# Cobro_Torniquete.net
KiCad netlist of a schematic drawn in EAGLE
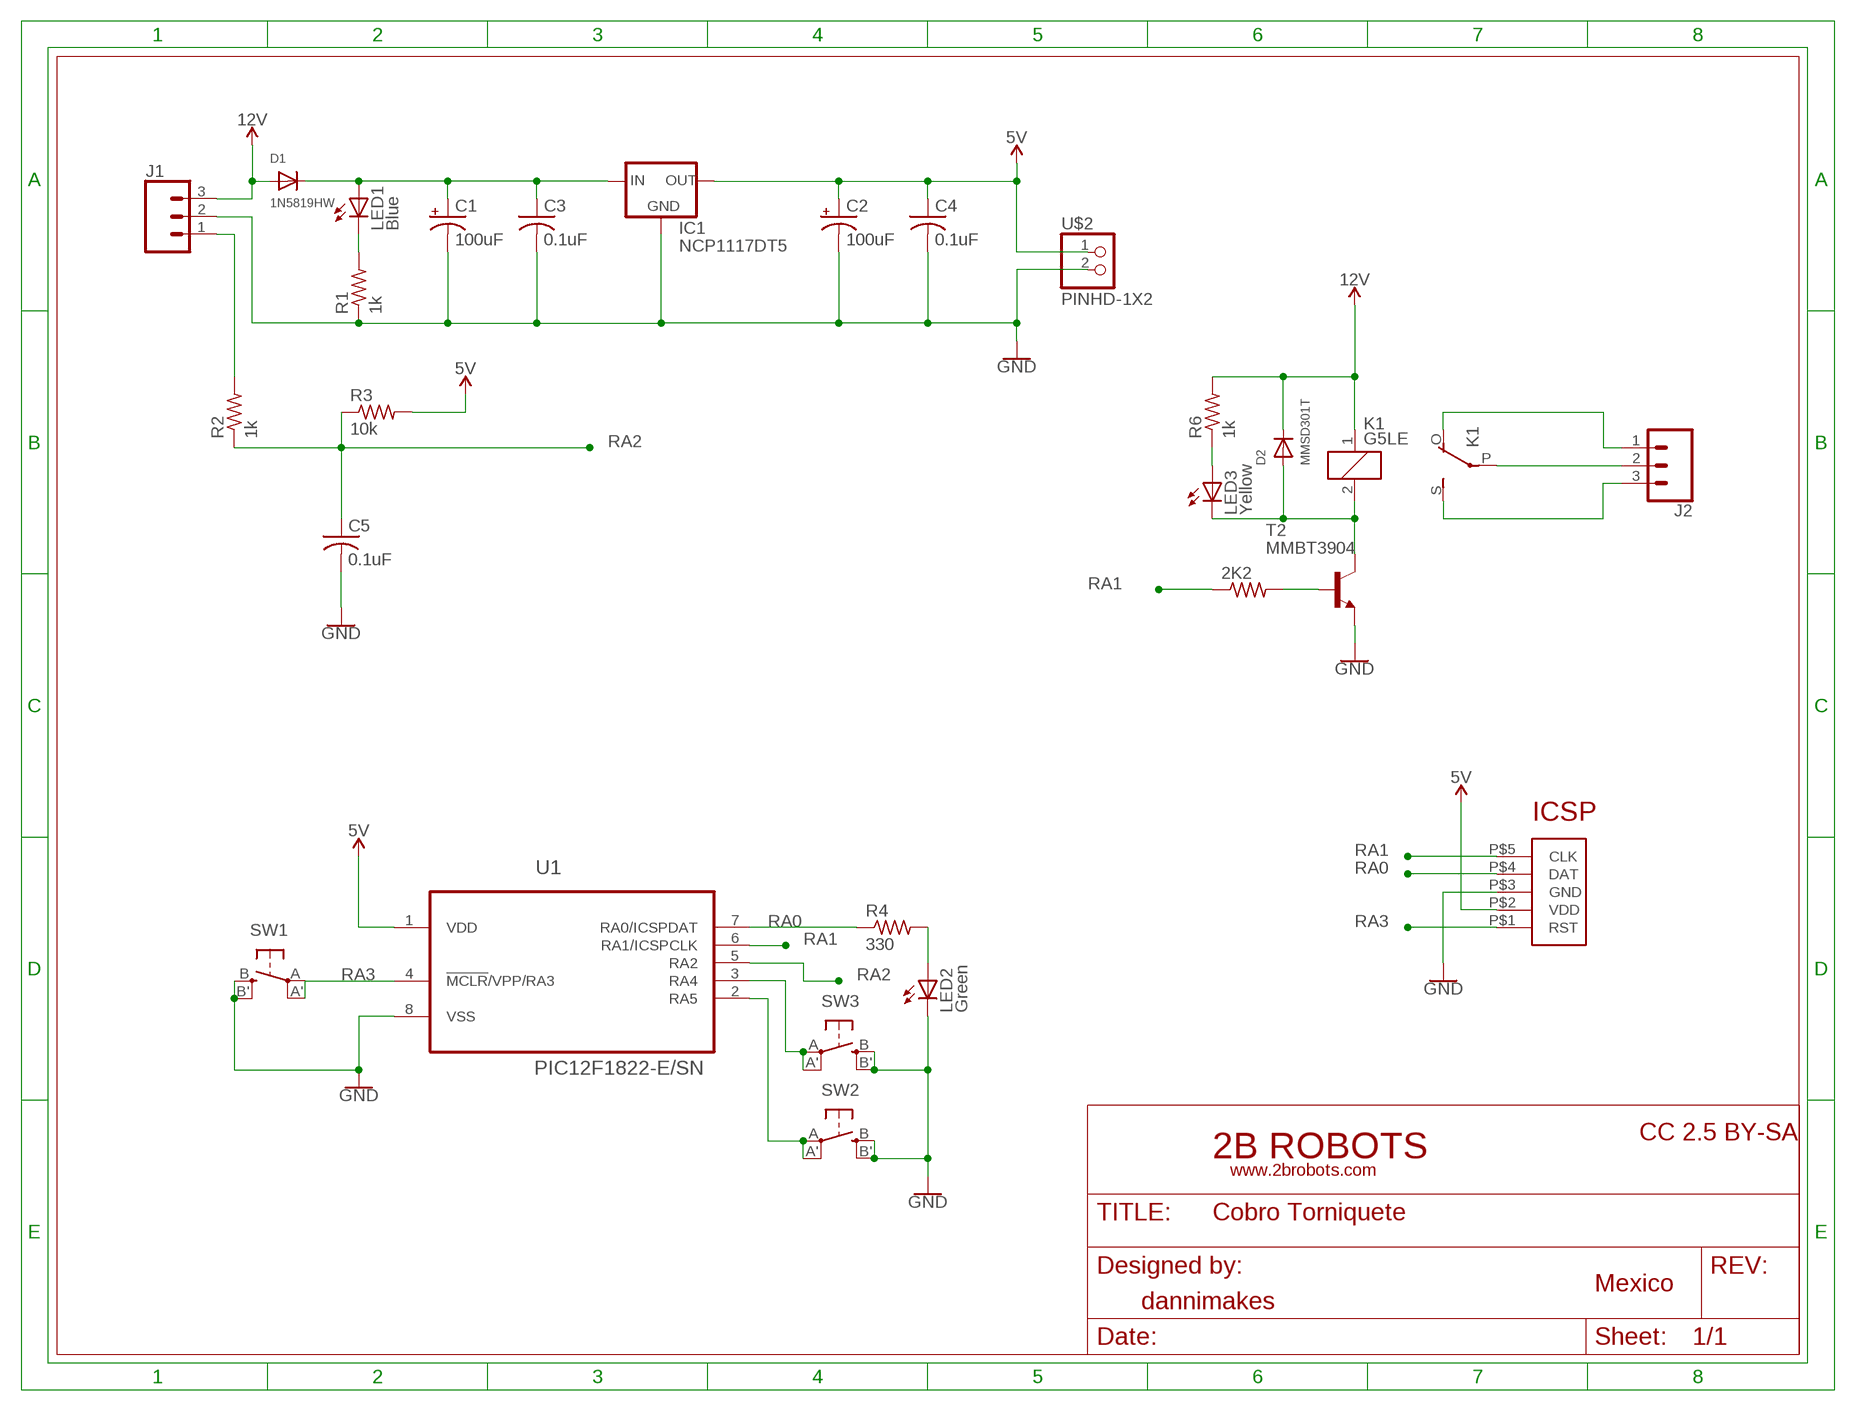
[diagram p0: schematic, sheet 1]

(export (version "E")
  (design (tool "Eeschema 10.0.6"))
  (components
    (comp (ref "2K2")
      (value "R-US_R0805")
      (footprint "eagle-import:R0805")
      (libsource (lib "eagle-import") (part "R-US_R0805"))
    )
    (comp (ref "C1")
      (value "100uF")
      (footprint "eagle-import:140CLH-0810")
      (libsource (lib "eagle-import") (part "CPOL-US140CLH-0810"))
    )
    (comp (ref "C2")
      (value "100uF")
      (footprint "eagle-import:140CLH-0810")
      (libsource (lib "eagle-import") (part "CPOL-US140CLH-0810"))
    )
    (comp (ref "C3")
      (value "0.1uF")
      (footprint "eagle-import:C0603K")
      (libsource (lib "eagle-import") (part "C-USC0603K"))
    )
    (comp (ref "C4")
      (value "0.1uF")
      (footprint "eagle-import:C0603K")
      (libsource (lib "eagle-import") (part "C-USC0603K"))
    )
    (comp (ref "C5")
      (value "0.1uF")
      (footprint "eagle-import:C0603K")
      (libsource (lib "eagle-import") (part "C-USC0603K"))
    )
    (comp (ref "D1")
      (value "1N5819HW")
      (footprint "eagle-import:SOD-123")
      (libsource (lib "eagle-import") (part "DIODESOD-123"))
    )
    (comp (ref "D2")
      (value "MMSD301T")
      (footprint "eagle-import:SOD-123")
      (libsource (lib "eagle-import") (part "DIODESOD-123"))
    )
    (comp (ref "IC1")
      (value "NCP1117DT5")
      (footprint "eagle-import:TO252")
      (libsource (lib "eagle-import") (part "LM1117TO252"))
    )
    (comp (ref "J1")
      (value "CONN_03-SCREW-5MM")
      (footprint "eagle-import:SCREWTERMINAL-5MM-3")
      (libsource (lib "eagle-import") (part "CONN_03-SCREW-5MM"))
    )
    (comp (ref "J2")
      (value "CONN_03-SCREW-5MM")
      (footprint "eagle-import:SCREWTERMINAL-5MM-3")
      (libsource (lib "eagle-import") (part "CONN_03-SCREW-5MM"))
    )
    (comp (ref "K1")
      (value "G5LE")
      (footprint "eagle-import:G5LE")
      (libsource (lib "eagle-import") (part "G5LE"))
    )
    (comp (ref "LED1")
      (value "Blue")
      (footprint "eagle-import:CHIPLED_1206")
      (libsource (lib "eagle-import") (part "LEDCHIPLED_1206"))
    )
    (comp (ref "LED2")
      (value "Green")
      (footprint "eagle-import:CHIPLED_1206")
      (libsource (lib "eagle-import") (part "LEDCHIPLED_1206"))
    )
    (comp (ref "LED3")
      (value "Yellow")
      (footprint "eagle-import:CHIPLED_1206")
      (libsource (lib "eagle-import") (part "LEDCHIPLED_1206"))
    )
    (comp (ref "R1")
      (value "1k")
      (footprint "eagle-import:R0805")
      (libsource (lib "eagle-import") (part "R-US_R0805"))
    )
    (comp (ref "R2")
      (value "1k")
      (footprint "eagle-import:R0805")
      (libsource (lib "eagle-import") (part "R-US_R0805"))
    )
    (comp (ref "R3")
      (value "10k")
      (footprint "eagle-import:R0805")
      (libsource (lib "eagle-import") (part "R-US_R0805"))
    )
    (comp (ref "R4")
      (value "330")
      (footprint "eagle-import:R0805")
      (libsource (lib "eagle-import") (part "R-US_R0805"))
    )
    (comp (ref "R6")
      (value "1k")
      (footprint "eagle-import:R0805")
      (libsource (lib "eagle-import") (part "R-US_R0805"))
    )
    (comp (ref "SW1")
      (value "SPST_TACT-EVQQ2")
      (footprint "eagle-import:EVQ-Q2")
      (libsource (lib "eagle-import") (part "SPST_TACT-EVQQ2"))
    )
    (comp (ref "SW2")
      (value "SPST_TACT-EVQQ2")
      (footprint "eagle-import:EVQ-Q2")
      (libsource (lib "eagle-import") (part "SPST_TACT-EVQQ2"))
    )
    (comp (ref "SW3")
      (value "SPST_TACT-EVQQ2")
      (footprint "eagle-import:EVQ-Q2")
      (libsource (lib "eagle-import") (part "SPST_TACT-EVQQ2"))
    )
    (comp (ref "T2")
      (value "MMBT3904")
      (footprint "eagle-import:SOT23-BEC")
      (libsource (lib "eagle-import") (part "-NPN-SOT23-BECMMBT3904LT1"))
    )
    (comp (ref "U$1")
      (value "ICSP_POGO")
      (footprint "eagle-import:ICSP_POGO")
      (libsource (lib "eagle-import") (part "ICSP_POGO"))
    )
    (comp (ref "U$2")
      (value "PINHD-1X2")
      (footprint "eagle-import:1X2")
      (libsource (lib "eagle-import") (part "PINHD-1X2"))
    )
    (comp (ref "U1")
      (value "PIC12F1822-E/SN")
      (footprint "eagle-import:SOIC127P600X175-8N")
      (libsource (lib "eagle-import") (part "PIC12F1822-E/SN"))
    )
  )
  (nets
    (net (code "1") (name "/RA0") (class "Default")
      (node (ref "R4") (pin "1") (pinfunction "1_1") (pintype "passive"))
      (node (ref "U$1") (pin "P$4") (pinfunction "DAT_P$4") (pintype "bidirectional"))
      (node (ref "U1") (pin "7") (pinfunction "RA0/ICSPDAT_7") (pintype "bidirectional"))
    )
    (net (code "2") (name "/RA1") (class "Default")
      (node (ref "2K2") (pin "1") (pinfunction "1_1") (pintype "passive"))
      (node (ref "U$1") (pin "P$5") (pinfunction "CLK_P$5") (pintype "bidirectional"))
      (node (ref "U1") (pin "6") (pinfunction "RA1/ICSPCLK_6") (pintype "bidirectional"))
    )
    (net (code "3") (name "/RA2") (class "Default")
      (node (ref "C5") (pin "1") (pinfunction "1_1") (pintype "passive"))
      (node (ref "R2") (pin "1") (pinfunction "1_1") (pintype "passive"))
      (node (ref "R3") (pin "1") (pinfunction "1_1") (pintype "passive"))
      (node (ref "U1") (pin "5") (pinfunction "RA2_5") (pintype "bidirectional"))
    )
    (net (code "4") (name "/RA3") (class "Default")
      (node (ref "SW1") (pin "A") (pinfunction "P_A") (pintype "passive"))
      (node (ref "SW1") (pin "A'") (pinfunction "P1_A'") (pintype "passive"))
      (node (ref "U$1") (pin "P$1") (pinfunction "RST_P$1") (pintype "bidirectional"))
      (node (ref "U1") (pin "4") (pinfunction "~{MCLR}/VPP/RA3_4") (pintype "input"))
    )
    (net (code "5") (name "5V") (class "Default")
      (node (ref "C2") (pin "+") (pinfunction "+_+") (pintype "passive"))
      (node (ref "C4") (pin "1") (pinfunction "1_1") (pintype "passive"))
      (node (ref "IC1") (pin "3") (pinfunction "OUT_3") (pintype "passive"))
      (node (ref "R3") (pin "2") (pinfunction "2_2") (pintype "passive"))
      (node (ref "U$1") (pin "P$2") (pinfunction "VDD_P$2") (pintype "bidirectional"))
      (node (ref "U$2") (pin "1") (pinfunction "1_1") (pintype "passive"))
      (node (ref "U1") (pin "1") (pinfunction "VDD_1") (pintype "power_in"))
    )
    (net (code "6") (name "12V") (class "Default")
      (node (ref "D1") (pin "A") (pinfunction "A_A") (pintype "passive"))
      (node (ref "D2") (pin "C") (pinfunction "C_C") (pintype "passive"))
      (node (ref "J1") (pin "3") (pinfunction "3_3") (pintype "passive"))
      (node (ref "K1") (pin "1") (pinfunction "1_1") (pintype "passive"))
      (node (ref "R6") (pin "2") (pinfunction "2_2") (pintype "passive"))
    )
    (net (code "7") (name "GND") (class "Default")
      (node (ref "C1") (pin "-") (pinfunction "-_-") (pintype "passive"))
      (node (ref "C2") (pin "-") (pinfunction "-_-") (pintype "passive"))
      (node (ref "C3") (pin "2") (pinfunction "2_2") (pintype "passive"))
      (node (ref "C4") (pin "2") (pinfunction "2_2") (pintype "passive"))
      (node (ref "C5") (pin "2") (pinfunction "2_2") (pintype "passive"))
      (node (ref "IC1") (pin "1") (pinfunction "GND_1") (pintype "input"))
      (node (ref "J1") (pin "2") (pinfunction "2_2") (pintype "passive"))
      (node (ref "LED2") (pin "C") (pinfunction "C_C") (pintype "passive"))
      (node (ref "R1") (pin "1") (pinfunction "1_1") (pintype "passive"))
      (node (ref "SW1") (pin "B") (pinfunction "S_B") (pintype "passive"))
      (node (ref "SW1") (pin "B'") (pinfunction "S1_B'") (pintype "passive"))
      (node (ref "SW2") (pin "B") (pinfunction "S_B") (pintype "passive"))
      (node (ref "SW2") (pin "B'") (pinfunction "S1_B'") (pintype "passive"))
      (node (ref "SW3") (pin "B") (pinfunction "S_B") (pintype "passive"))
      (node (ref "SW3") (pin "B'") (pinfunction "S1_B'") (pintype "passive"))
      (node (ref "T2") (pin "E") (pinfunction "E_E") (pintype "passive"))
      (node (ref "U$1") (pin "P$3") (pinfunction "GND_P$3") (pintype "bidirectional"))
      (node (ref "U$2") (pin "2") (pinfunction "2_2") (pintype "passive"))
      (node (ref "U1") (pin "8") (pinfunction "VSS_8") (pintype "power_in"))
    )
    (net (code "8") (name "Net-(2K2-Pad2)") (class "Default")
      (node (ref "2K2") (pin "2") (pinfunction "2_2") (pintype "passive"))
      (node (ref "T2") (pin "B") (pinfunction "B_B") (pintype "passive"))
    )
    (net (code "9") (name "Net-(D2-PadA)") (class "Default")
      (node (ref "D2") (pin "A") (pinfunction "A_A") (pintype "passive"))
      (node (ref "K1") (pin "2") (pinfunction "2_2") (pintype "passive"))
      (node (ref "LED3") (pin "C") (pinfunction "C_C") (pintype "passive"))
      (node (ref "T2") (pin "C") (pinfunction "C_C") (pintype "passive"))
    )
    (net (code "10") (name "Net-(IC1-IN)") (class "Default")
      (node (ref "C1") (pin "+") (pinfunction "+_+") (pintype "passive"))
      (node (ref "C3") (pin "1") (pinfunction "1_1") (pintype "passive"))
      (node (ref "D1") (pin "C") (pinfunction "C_C") (pintype "passive"))
      (node (ref "IC1") (pin "2") (pinfunction "IN_2") (pintype "input"))
      (node (ref "LED1") (pin "A") (pinfunction "A_A") (pintype "passive"))
    )
    (net (code "11") (name "Net-(J1-Pad1)") (class "Default")
      (node (ref "J1") (pin "1") (pinfunction "1_1") (pintype "passive"))
      (node (ref "R2") (pin "2") (pinfunction "2_2") (pintype "passive"))
    )
    (net (code "12") (name "Net-(J2-Pad1)") (class "Default")
      (node (ref "J2") (pin "1") (pinfunction "1_1") (pintype "passive"))
      (node (ref "K1") (pin "O") (pinfunction "O_O") (pintype "passive"))
    )
    (net (code "13") (name "Net-(J2-Pad2)") (class "Default")
      (node (ref "J2") (pin "2") (pinfunction "2_2") (pintype "passive"))
      (node (ref "K1") (pin "P") (pinfunction "P_P") (pintype "passive"))
    )
    (net (code "14") (name "Net-(J2-Pad3)") (class "Default")
      (node (ref "J2") (pin "3") (pinfunction "3_3") (pintype "passive"))
      (node (ref "K1") (pin "S") (pinfunction "S_S") (pintype "passive"))
    )
    (net (code "15") (name "Net-(LED1-PadC)") (class "Default")
      (node (ref "LED1") (pin "C") (pinfunction "C_C") (pintype "passive"))
      (node (ref "R1") (pin "2") (pinfunction "2_2") (pintype "passive"))
    )
    (net (code "16") (name "Net-(LED2-PadA)") (class "Default")
      (node (ref "LED2") (pin "A") (pinfunction "A_A") (pintype "passive"))
      (node (ref "R4") (pin "2") (pinfunction "2_2") (pintype "passive"))
    )
    (net (code "17") (name "Net-(LED3-PadA)") (class "Default")
      (node (ref "LED3") (pin "A") (pinfunction "A_A") (pintype "passive"))
      (node (ref "R6") (pin "1") (pinfunction "1_1") (pintype "passive"))
    )
    (net (code "18") (name "Net-(SW2-P)") (class "Default")
      (node (ref "SW2") (pin "A") (pinfunction "P_A") (pintype "passive"))
      (node (ref "SW2") (pin "A'") (pinfunction "P1_A'") (pintype "passive"))
      (node (ref "U1") (pin "2") (pinfunction "RA5_2") (pintype "bidirectional"))
    )
    (net (code "19") (name "Net-(SW3-P)") (class "Default")
      (node (ref "SW3") (pin "A") (pinfunction "P_A") (pintype "passive"))
      (node (ref "SW3") (pin "A'") (pinfunction "P1_A'") (pintype "passive"))
      (node (ref "U1") (pin "3") (pinfunction "RA4_3") (pintype "bidirectional"))
    )
  )
)
